# VUE_PIC32_v1_0_USB-Serial.net
KiCad netlist of a schematic drawn in Altium Designer
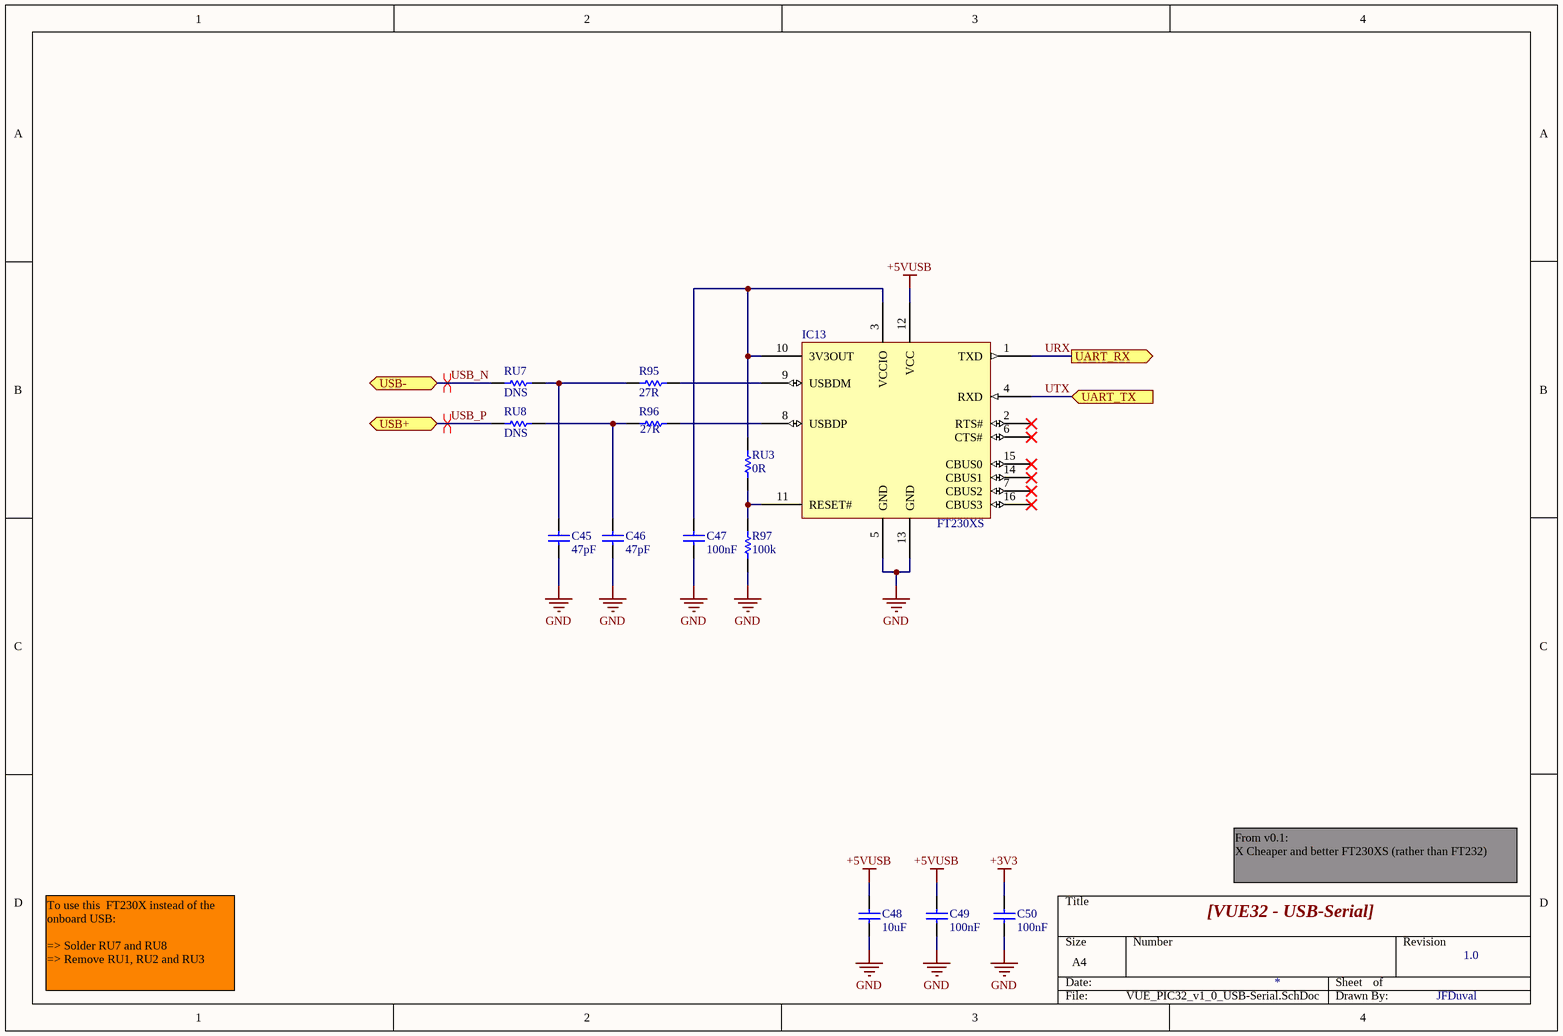
[diagram p0: VUE_PIC32_v1_0_USB-Serial.SchDoc]

(export (version "E")
  (design (tool "Eeschema 10.0.6"))
  (components
    (comp (ref "C45")
      (value "47pF")
      (footprint "0402C")
      (description "CAP CER 47PF 50V 5% NP0 0402")
      (fields (field (name "MFG") "TDK") (field (name "MFGPARTNUMBER") "CGA2B2C0G1H470J"))
      (libsource (lib "JFD_Cap") (part "CAP_TDK_C_0402_47pF_50V"))
    )
    (comp (ref "C46")
      (value "47pF")
      (footprint "0402C")
      (description "CAP CER 47PF 50V 5% NP0 0402")
      (fields (field (name "MFG") "TDK") (field (name "MFGPARTNUMBER") "CGA2B2C0G1H470J"))
      (libsource (lib "JFD_Cap") (part "CAP_TDK_C_0402_47pF_50V"))
    )
    (comp (ref "C47")
      (value "100nF")
      (footprint "0402C")
      (description "CAP CER 0.1UF 25V Y5V 0402")
      (fields (field (name "MFG") "TDK") (field (name "MFGPARTNUMBER") "C1005Y5V1E104Z"))
      (libsource (lib "JFD_Cap") (part "CAP_TDK_C_0402_100nF_25V"))
    )
    (comp (ref "C48")
      (value "10uF")
      (footprint "0805C")
      (description "CAP CER 10UF 16V Y5V 0805")
      (fields (field (name "MFG") "Murata") (field (name "MFGPARTNUMBER") "GRM21BF51C106ZE15L"))
      (libsource (lib "JFD_Cap") (part "CAP_MURATA_C_0805_10uF_16V"))
    )
    (comp (ref "C49")
      (value "100nF")
      (footprint "0402C")
      (description "CAP CER 0.1UF 25V Y5V 0402")
      (fields (field (name "MFG") "TDK") (field (name "MFGPARTNUMBER") "C1005Y5V1E104Z"))
      (libsource (lib "JFD_Cap") (part "CAP_TDK_C_0402_100nF_25V"))
    )
    (comp (ref "C50")
      (value "100nF")
      (footprint "0402C")
      (description "CAP CER 0.1UF 25V Y5V 0402")
      (fields (field (name "MFG") "TDK") (field (name "MFGPARTNUMBER") "C1005Y5V1E104Z"))
      (libsource (lib "JFD_Cap") (part "CAP_TDK_C_0402_100nF_25V"))
    )
    (comp (ref "IC13")
      (value "FT230XS")
      (footprint "SSOP16")
      (description "IC USB ERIAL BASIC UART SSOP-16")
      (fields (field (name "MFG") "FTDI"))
      (libsource (lib "JFD_IC") (part "IC_FTDI_FT230XS_USB_UART_SSOP16"))
    )
    (comp (ref "R95")
      (value "27R")
      (footprint "0402")
      (description "RES 27.0 OHM 1/10W 1% 0402 SMD")
      (fields (field (name "MFG") "Panasonic") (field (name "MFGPARTNUMBER") "ERJ-2RKF27R0X"))
      (libsource (lib "JFD_Res") (part "RES_PANASONIC_0402_27R_1PCT"))
    )
    (comp (ref "R96")
      (value "27R")
      (footprint "0402")
      (description "RES 27.0 OHM 1/10W 1% 0402 SMD")
      (fields (field (name "MFG") "Panasonic") (field (name "MFGPARTNUMBER") "ERJ-2RKF27R0X"))
      (libsource (lib "JFD_Res") (part "RES_PANASONIC_0402_27R_1PCT"))
    )
    (comp (ref "R97")
      (value "100k")
      (footprint "0402")
      (description "RES 100K OHM 1/16W 1% 0402 SMD")
      (fields (field (name "MFG") "Yageo") (field (name "MFGPARTNUMBER") "RC0402FR-07100KL"))
      (libsource (lib "JFD_Res") (part "RES_YAGEO_0402_100K_1PCT"))
    )
    (comp (ref "RU3")
      (value "0R")
      (footprint "0402")
      (description "RES 0.0 OHM 1/16W 0402 SMD")
      (fields (field (name "MFG") "Yageo") (field (name "MFGPARTNUMBER") "RC0402JR-070RL"))
      (libsource (lib "JFD_Res") (part "RES_YAGEO_0402_0R_1PCT"))
    )
    (comp (ref "RU7")
      (value "DNS")
      (footprint "0603")
      (description "Optional jumper - Do Not Solder")
      (fields (field (name "MFG") "NULL"))
      (libsource (lib "JFD_Res") (part "RES_DO_NOT_SOLDER_DNS_0603"))
    )
    (comp (ref "RU8")
      (value "DNS")
      (footprint "0603")
      (description "Optional jumper - Do Not Solder")
      (fields (field (name "MFG") "NULL"))
      (libsource (lib "JFD_Res") (part "RES_DO_NOT_SOLDER_DNS_0603"))
    )
  )
  (nets
    (net (code "1") (name "+3V3") (class "Default")
      (node (ref "C50") (pin "2") (pinfunction "2_2") (pintype "passive"))
    )
    (net (code "2") (name "+5VUSB") (class "Default")
      (node (ref "C48") (pin "2") (pinfunction "2_2") (pintype "passive"))
      (node (ref "C49") (pin "2") (pinfunction "2_2") (pintype "passive"))
      (node (ref "IC13") (pin "12") (pinfunction "VCC_12") (pintype "power_in"))
    )
    (net (code "3") (name "/URX") (class "Default")
      (node (ref "IC13") (pin "1") (pinfunction "TXD_1") (pintype "output"))
    )
    (net (code "4") (name "/USB_N") (class "Default")
      (node (ref "RU7") (pin "1") (pinfunction "1_1") (pintype "passive"))
    )
    (net (code "5") (name "/USB_P") (class "Default")
      (node (ref "RU8") (pin "1") (pinfunction "1_1") (pintype "passive"))
    )
    (net (code "6") (name "/UTX") (class "Default")
      (node (ref "IC13") (pin "4") (pinfunction "RXD_4") (pintype "input"))
    )
    (net (code "7") (name "GND") (class "Default")
      (node (ref "C45") (pin "1") (pinfunction "1_1") (pintype "passive"))
      (node (ref "C46") (pin "1") (pinfunction "1_1") (pintype "passive"))
      (node (ref "C47") (pin "1") (pinfunction "1_1") (pintype "passive"))
      (node (ref "C48") (pin "1") (pinfunction "1_1") (pintype "passive"))
      (node (ref "C49") (pin "1") (pinfunction "1_1") (pintype "passive"))
      (node (ref "C50") (pin "1") (pinfunction "1_1") (pintype "passive"))
      (node (ref "IC13") (pin "13") (pinfunction "GND_13") (pintype "power_in"))
      (node (ref "IC13") (pin "5") (pinfunction "GND_5") (pintype "power_in"))
      (node (ref "R97") (pin "1") (pinfunction "1_1") (pintype "passive"))
    )
    (net (code "8") (name "Net-(C45-Pad2)") (class "Default")
      (node (ref "C45") (pin "2") (pinfunction "2_2") (pintype "passive"))
      (node (ref "R95") (pin "1") (pinfunction "1_1") (pintype "passive"))
      (node (ref "RU7") (pin "2") (pinfunction "2_2") (pintype "passive"))
    )
    (net (code "9") (name "Net-(C46-Pad2)") (class "Default")
      (node (ref "C46") (pin "2") (pinfunction "2_2") (pintype "passive"))
      (node (ref "R96") (pin "1") (pinfunction "1_1") (pintype "passive"))
      (node (ref "RU8") (pin "2") (pinfunction "2_2") (pintype "passive"))
    )
    (net (code "10") (name "Net-(IC13-3V3OUT)") (class "Default")
      (node (ref "C47") (pin "2") (pinfunction "2_2") (pintype "passive"))
      (node (ref "IC13") (pin "10") (pinfunction "3V3OUT_10") (pintype "power_in"))
      (node (ref "IC13") (pin "3") (pinfunction "VCCIO_3") (pintype "power_in"))
      (node (ref "RU3") (pin "1") (pinfunction "1_1") (pintype "passive"))
    )
    (net (code "11") (name "Net-(IC13-RESET#)") (class "Default")
      (node (ref "IC13") (pin "11") (pinfunction "RESET#_11") (pintype "passive"))
      (node (ref "R97") (pin "2") (pinfunction "2_2") (pintype "passive"))
      (node (ref "RU3") (pin "2") (pinfunction "2_2") (pintype "passive"))
    )
    (net (code "12") (name "Net-(IC13-USBDM)") (class "Default")
      (node (ref "IC13") (pin "9") (pinfunction "USBDM_9") (pintype "bidirectional"))
      (node (ref "R95") (pin "2") (pinfunction "2_2") (pintype "passive"))
    )
    (net (code "13") (name "Net-(IC13-USBDP)") (class "Default")
      (node (ref "IC13") (pin "8") (pinfunction "USBDP_8") (pintype "bidirectional"))
      (node (ref "R96") (pin "2") (pinfunction "2_2") (pintype "passive"))
    )
    (net (code "14") (name "unconnected-(IC13-CBUS0-Pad15)") (class "Default")
      (node (ref "IC13") (pin "15") (pinfunction "CBUS0_15") (pintype "bidirectional+no_connect"))
    )
    (net (code "15") (name "unconnected-(IC13-CBUS1-Pad14)") (class "Default")
      (node (ref "IC13") (pin "14") (pinfunction "CBUS1_14") (pintype "bidirectional+no_connect"))
    )
    (net (code "16") (name "unconnected-(IC13-CBUS2-Pad7)") (class "Default")
      (node (ref "IC13") (pin "7") (pinfunction "CBUS2_7") (pintype "bidirectional+no_connect"))
    )
    (net (code "17") (name "unconnected-(IC13-CBUS3-Pad16)") (class "Default")
      (node (ref "IC13") (pin "16") (pinfunction "CBUS3_16") (pintype "bidirectional+no_connect"))
    )
    (net (code "18") (name "unconnected-(IC13-CTS#-Pad6)") (class "Default")
      (node (ref "IC13") (pin "6") (pinfunction "CTS#_6") (pintype "bidirectional+no_connect"))
    )
    (net (code "19") (name "unconnected-(IC13-RTS#-Pad2)") (class "Default")
      (node (ref "IC13") (pin "2") (pinfunction "RTS#_2") (pintype "bidirectional+no_connect"))
    )
  )
)
